# Schematic.net
KiCad netlist of a schematic drawn in Altium Designer
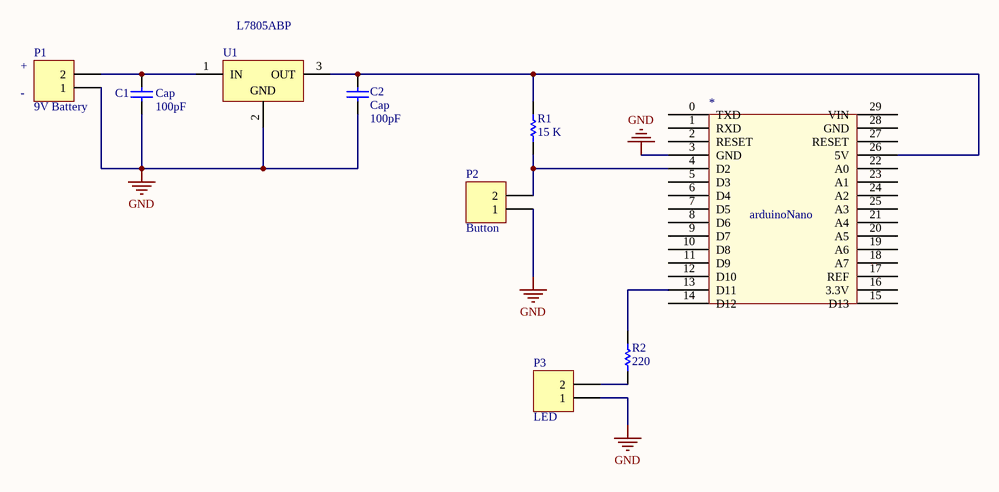
[diagram p0: Schematic.SchDoc]

(export (version "E")
  (design (tool "Eeschema 10.0.6"))
  (components
    (comp (ref "*")
      (value "arduinoNano")
      (footprint "Arduino nano")
      (libsource (lib "nanoArduino") (part "arduinoNano"))
    )
    (comp (ref "C1")
      (value "Cap")
      (footprint "RAD-0.3")
      (description "Capacitor")
      (fields (field (name "ALTIUM_VALUE") "100pF") (field (name "PUBLISHER") "Altium Limited"))
      (libsource (lib "Miscellaneous Devices") (part "Cap"))
    )
    (comp (ref "C2")
      (value "Cap")
      (footprint "RAD-0.3")
      (description "Capacitor")
      (fields (field (name "ALTIUM_VALUE") "100pF") (field (name "PUBLISHER") "Altium Limited"))
      (libsource (lib "Miscellaneous Devices") (part "Cap"))
    )
    (comp (ref "P1")
      (value "9V Battery")
      (footprint "HDR1X2")
      (description "Header, 2-Pin")
      (fields (field (name "PUBLISHER") "Altium Limited"))
      (libsource (lib "Miscellaneous Connectors") (part "Header 2"))
    )
    (comp (ref "P2")
      (value "Button")
      (footprint "HDR1X2")
      (description "Header, 2-Pin")
      (fields (field (name "PUBLISHER") "Altium Limited"))
      (libsource (lib "Miscellaneous Connectors") (part "Header 2"))
    )
    (comp (ref "P3")
      (value "LED")
      (footprint "HDR1X2")
      (description "Header, 2-Pin")
      (fields (field (name "PUBLISHER") "Altium Limited"))
      (libsource (lib "Miscellaneous Connectors") (part "Header 2"))
    )
    (comp (ref "R1")
      (value "15 K")
      (footprint "YFDZ-MFJRY13-2_M")
      (fields
        (field (name "PARTNUMBER") "MFJRY13T52051K00")
        (field (name "MANUFACTURER") "YingFa Electronics")
      )
      (libsource (lib "Altium Content Vault") (part "YFDZ-RES-2"))
    )
    (comp (ref "R2")
      (value "220")
      (footprint "YFDZ-MFJRY13-2_M")
      (fields
        (field (name "PARTNUMBER") "MFJRY13T52051K00")
        (field (name "MANUFACTURER") "YingFa Electronics")
      )
      (libsource (lib "Altium Content Vault") (part "YFDZ-RES-2"))
    )
    (comp (ref "U1")
      (value "L7805ABP")
      (footprint "TO220FP")
      (description "Positive Voltage Regulator, 5V, 3-Pin TO-220FP")
      (libsource (lib "Altium Content Vault") (part "PM-REG-L4940-SIL3"))
    )
  )
  (nets
    (net (code "1") (name "GND") (class "Default")
      (node (ref "*") (pin "3") (pinfunction "GND_3") (pintype "passive"))
      (node (ref "C1") (pin "2") (pinfunction "2_2") (pintype "passive"))
      (node (ref "C2") (pin "1") (pinfunction "1_1") (pintype "passive"))
      (node (ref "P1") (pin "1") (pinfunction "1_1") (pintype "passive"))
      (node (ref "P2") (pin "1") (pinfunction "1_1") (pintype "passive"))
      (node (ref "P3") (pin "1") (pinfunction "1_1") (pintype "passive"))
      (node (ref "U1") (pin "2") (pinfunction "GND_2") (pintype "power_in"))
    )
    (net (code "2") (name "Net-(*-5V)") (class "Default")
      (node (ref "*") (pin "26") (pinfunction "5V_26") (pintype "passive"))
      (node (ref "C2") (pin "2") (pinfunction "2_2") (pintype "passive"))
      (node (ref "R1") (pin "2") (pinfunction "2_2") (pintype "passive"))
      (node (ref "U1") (pin "3") (pinfunction "OUT_3") (pintype "power_in"))
    )
    (net (code "3") (name "Net-(*-D2)") (class "Default")
      (node (ref "*") (pin "4") (pinfunction "D2_4") (pintype "passive"))
      (node (ref "P2") (pin "2") (pinfunction "2_2") (pintype "passive"))
      (node (ref "R1") (pin "1") (pinfunction "1_1") (pintype "passive"))
    )
    (net (code "4") (name "Net-(*-D11)") (class "Default")
      (node (ref "*") (pin "13") (pinfunction "D11_13") (pintype "passive"))
      (node (ref "R2") (pin "2") (pinfunction "2_2") (pintype "passive"))
    )
    (net (code "5") (name "Net-(P3-Pad2)") (class "Default")
      (node (ref "P3") (pin "2") (pinfunction "2_2") (pintype "passive"))
      (node (ref "R2") (pin "1") (pinfunction "1_1") (pintype "passive"))
    )
    (net (code "6") (name "Net-(U1-IN)") (class "Default")
      (node (ref "C1") (pin "1") (pinfunction "1_1") (pintype "passive"))
      (node (ref "P1") (pin "2") (pinfunction "2_2") (pintype "passive"))
      (node (ref "U1") (pin "1") (pinfunction "IN_1") (pintype "power_in"))
    )
    (net (code "7") (name "unconnected-(*-3.3V-Pad16)") (class "Default")
      (node (ref "*") (pin "16") (pinfunction "3.3V_16") (pintype "passive"))
    )
    (net (code "8") (name "unconnected-(*-A0-Pad22)") (class "Default")
      (node (ref "*") (pin "22") (pinfunction "A0_22") (pintype "passive"))
    )
    (net (code "9") (name "unconnected-(*-A1-Pad23)") (class "Default")
      (node (ref "*") (pin "23") (pinfunction "A1_23") (pintype "passive"))
    )
    (net (code "10") (name "unconnected-(*-A2-Pad24)") (class "Default")
      (node (ref "*") (pin "24") (pinfunction "A2_24") (pintype "passive"))
    )
    (net (code "11") (name "unconnected-(*-A3-Pad25)") (class "Default")
      (node (ref "*") (pin "25") (pinfunction "A3_25") (pintype "passive"))
    )
    (net (code "12") (name "unconnected-(*-A4-Pad21)") (class "Default")
      (node (ref "*") (pin "21") (pinfunction "A4_21") (pintype "passive"))
    )
    (net (code "13") (name "unconnected-(*-A5-Pad20)") (class "Default")
      (node (ref "*") (pin "20") (pinfunction "A5_20") (pintype "passive"))
    )
    (net (code "14") (name "unconnected-(*-A6-Pad19)") (class "Default")
      (node (ref "*") (pin "19") (pinfunction "A6_19") (pintype "passive"))
    )
    (net (code "15") (name "unconnected-(*-A7-Pad18)") (class "Default")
      (node (ref "*") (pin "18") (pinfunction "A7_18") (pintype "passive"))
    )
    (net (code "16") (name "unconnected-(*-D3-Pad5)") (class "Default")
      (node (ref "*") (pin "5") (pinfunction "D3_5") (pintype "passive"))
    )
    (net (code "17") (name "unconnected-(*-D4-Pad6)") (class "Default")
      (node (ref "*") (pin "6") (pinfunction "D4_6") (pintype "passive"))
    )
    (net (code "18") (name "unconnected-(*-D5-Pad7)") (class "Default")
      (node (ref "*") (pin "7") (pinfunction "D5_7") (pintype "passive"))
    )
    (net (code "19") (name "unconnected-(*-D6-Pad8)") (class "Default")
      (node (ref "*") (pin "8") (pinfunction "D6_8") (pintype "passive"))
    )
    (net (code "20") (name "unconnected-(*-D7-Pad9)") (class "Default")
      (node (ref "*") (pin "9") (pinfunction "D7_9") (pintype "passive"))
    )
    (net (code "21") (name "unconnected-(*-D8-Pad10)") (class "Default")
      (node (ref "*") (pin "10") (pinfunction "D8_10") (pintype "passive"))
    )
    (net (code "22") (name "unconnected-(*-D9-Pad11)") (class "Default")
      (node (ref "*") (pin "11") (pinfunction "D9_11") (pintype "passive"))
    )
    (net (code "23") (name "unconnected-(*-D10-Pad12)") (class "Default")
      (node (ref "*") (pin "12") (pinfunction "D10_12") (pintype "passive"))
    )
    (net (code "24") (name "unconnected-(*-D12-Pad14)") (class "Default")
      (node (ref "*") (pin "14") (pinfunction "D12_14") (pintype "passive"))
    )
    (net (code "25") (name "unconnected-(*-D13-Pad15)") (class "Default")
      (node (ref "*") (pin "15") (pinfunction "D13_15") (pintype "passive"))
    )
    (net (code "26") (name "unconnected-(*-GND-Pad28)") (class "Default")
      (node (ref "*") (pin "28") (pinfunction "GND_28") (pintype "passive"))
    )
    (net (code "27") (name "unconnected-(*-REF-Pad17)") (class "Default")
      (node (ref "*") (pin "17") (pinfunction "REF_17") (pintype "passive"))
    )
    (net (code "28") (name "unconnected-(*-RESET-Pad2)") (class "Default")
      (node (ref "*") (pin "2") (pinfunction "RESET_2") (pintype "passive"))
    )
    (net (code "29") (name "unconnected-(*-RESET-Pad27)") (class "Default")
      (node (ref "*") (pin "27") (pinfunction "RESET_27") (pintype "passive"))
    )
    (net (code "30") (name "unconnected-(*-RXD-Pad1)") (class "Default")
      (node (ref "*") (pin "1") (pinfunction "RXD_1") (pintype "passive"))
    )
    (net (code "31") (name "unconnected-(*-TXD-Pad0)") (class "Default")
      (node (ref "*") (pin "0") (pinfunction "TXD_0") (pintype "passive"))
    )
    (net (code "32") (name "unconnected-(*-VIN-Pad29)") (class "Default")
      (node (ref "*") (pin "29") (pinfunction "VIN_29") (pintype "passive"))
    )
  )
)
